# 780-00055_rev1_CPLD_SCH_NRES_RTD_board.net
KiCad netlist of a schematic drawn in Altium Designer
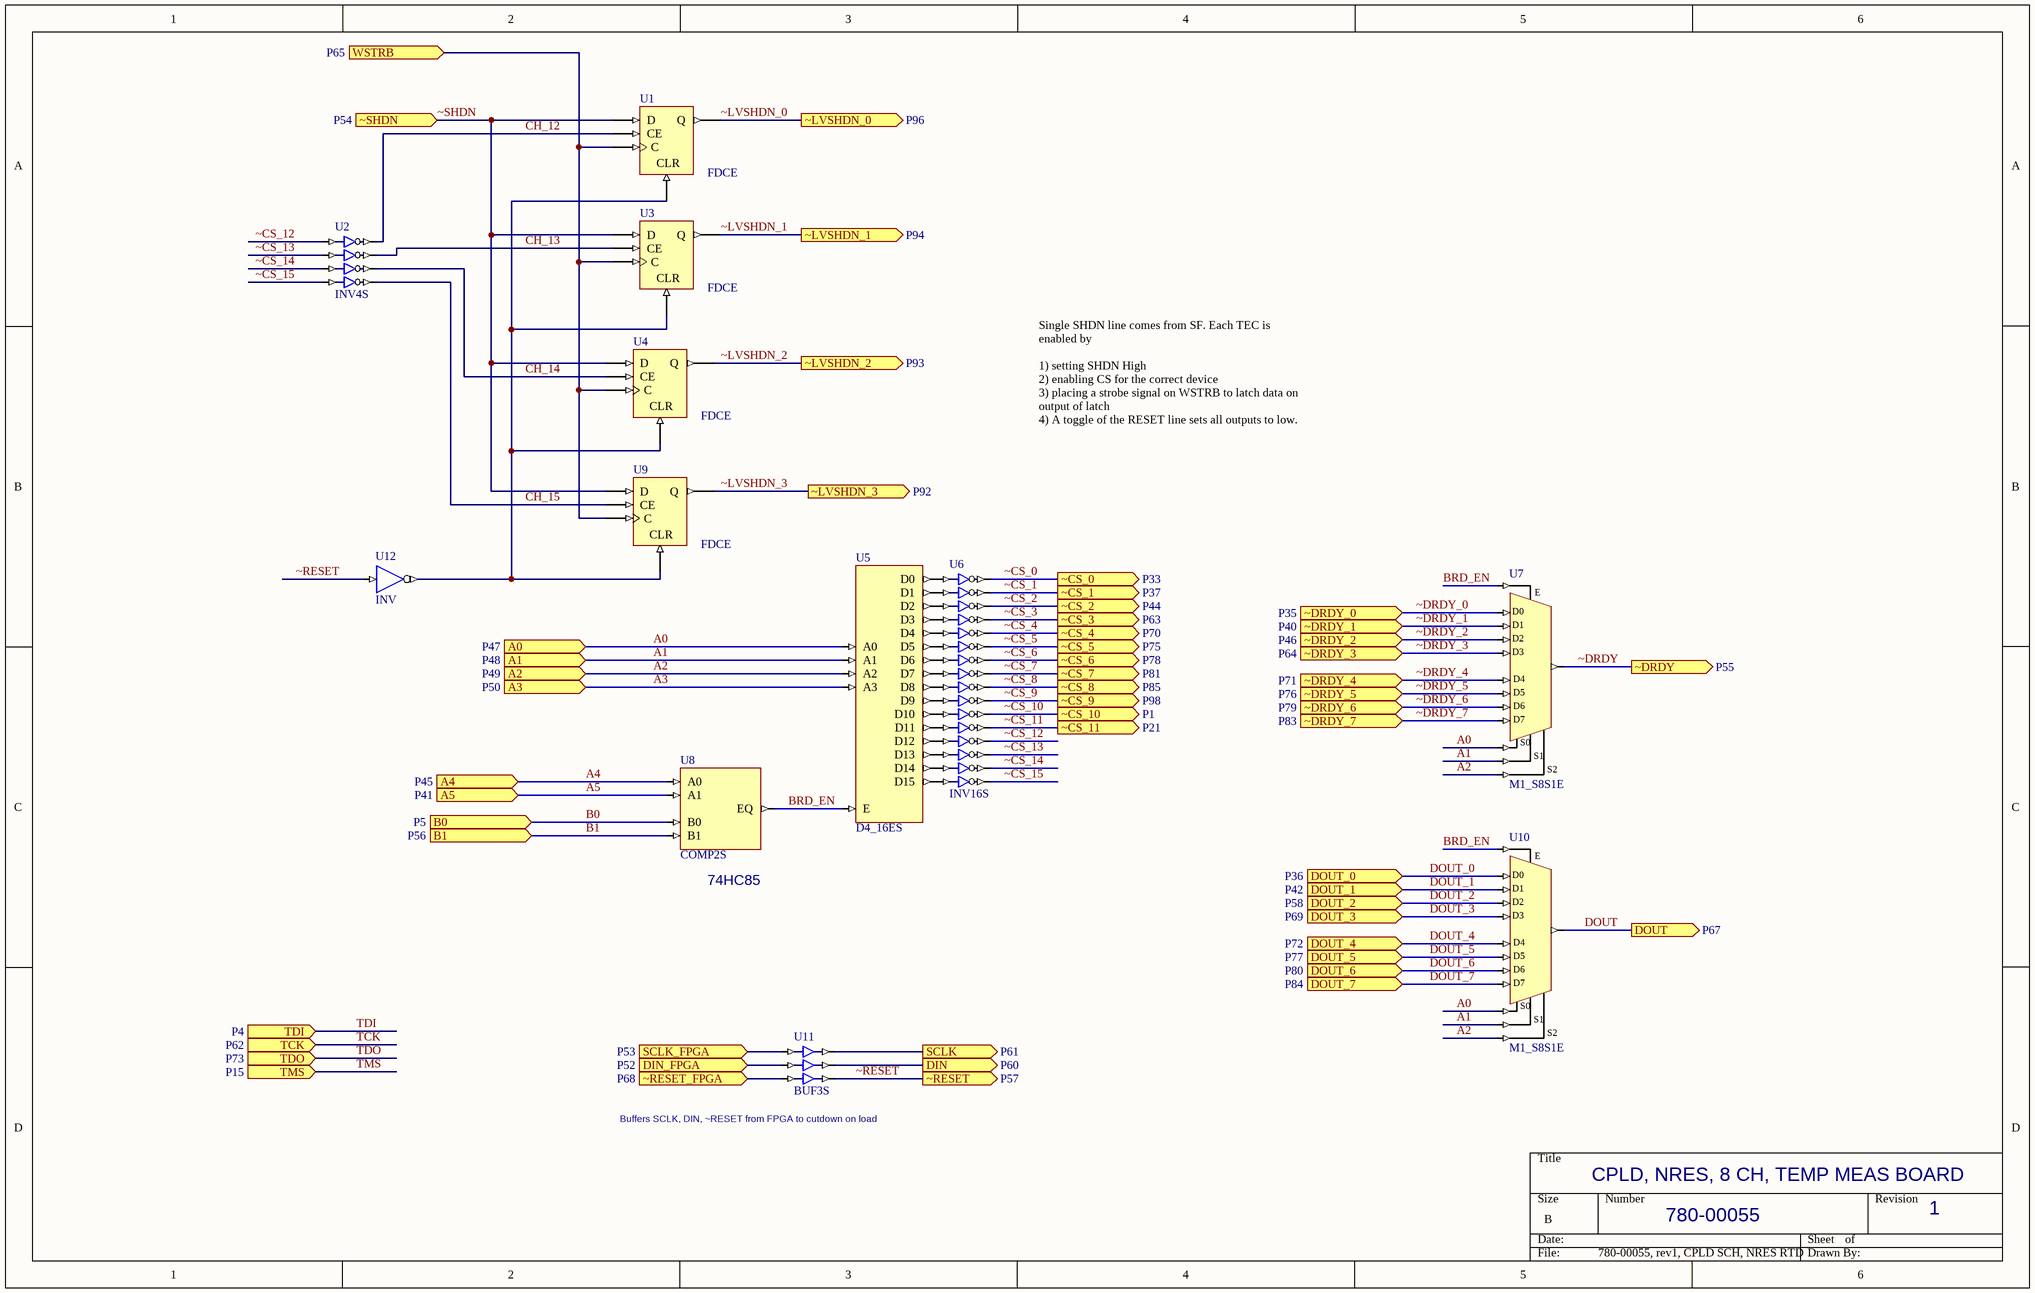
[diagram p0: 780-00055, rev1, CPLD SCH, NRES RTD board.SchDoc]

(export (version "E")
  (design (tool "Eeschema 10.0.6"))
  (components
    (comp (ref "U1")
      (value "FDCE")
      (description "D Flip-Flop with Clock Enable and Asynchronous Clear")
      (fields (field (name "PUBLISHER") "Altium Limited"))
      (libsource (lib "Xilinx CoolRunner-XPLA3 FPGA") (part "FDCE"))
    )
    (comp (ref "U2")
      (value "INV4S")
      (description "4-Bit Inverter, Single Pin Version")
      (fields (field (name "PUBLISHER") "Altium Limited"))
      (libsource (lib "FPGA Generic") (part "INV4S"))
    )
    (comp (ref "U3")
      (value "FDCE")
      (description "D Flip-Flop with Clock Enable and Asynchronous Clear")
      (fields (field (name "PUBLISHER") "Altium Limited"))
      (libsource (lib "Xilinx CoolRunner-XPLA3 FPGA") (part "FDCE"))
    )
    (comp (ref "U4")
      (value "FDCE")
      (description "D Flip-Flop with Clock Enable and Asynchronous Clear")
      (fields (field (name "PUBLISHER") "Altium Limited"))
      (libsource (lib "Xilinx CoolRunner-XPLA3 FPGA") (part "FDCE"))
    )
    (comp (ref "U5")
      (value "D4_16ES")
      (description "Binary 4- to 16-Bit Decoder with Enable, Single Pin Version")
      (fields (field (name "PUBLISHER") "Altium Limited"))
      (libsource (lib "FPGA Generic") (part "D4_16ES"))
    )
    (comp (ref "U6")
      (value "INV16S")
      (description "16-Bit Inverter, Single Pin Version")
      (fields (field (name "PUBLISHER") "Altium Limited"))
      (libsource (lib "FPGA Generic") (part "INV16S"))
    )
    (comp (ref "U7")
      (value "M1_S8S1E")
      (description "8x1-Single Wire to 1x1-Single Wire Multiplexer With Enable")
      (fields (field (name "PUBLISHER") "Altium Limited"))
      (libsource (lib "FPGA Generic") (part "M1_S8S1E"))
    )
    (comp (ref "U8")
      (value "COMP2S")
      (description "2-Bit Identity Comparator, Single Pin Version")
      (fields (field (name "PUBLISHER") "Altium Limited"))
      (libsource (lib "FPGA Generic") (part "COMP2S"))
    )
    (comp (ref "U9")
      (value "FDCE")
      (description "D Flip-Flop with Clock Enable and Asynchronous Clear")
      (fields (field (name "PUBLISHER") "Altium Limited"))
      (libsource (lib "Xilinx CoolRunner-XPLA3 FPGA") (part "FDCE"))
    )
    (comp (ref "U10")
      (value "M1_S8S1E")
      (description "8x1-Single Wire to 1x1-Single Wire Multiplexer With Enable")
      (fields (field (name "PUBLISHER") "Altium Limited"))
      (libsource (lib "FPGA Generic") (part "M1_S8S1E"))
    )
    (comp (ref "U11")
      (value "BUF3S")
      (description "3-Bit General Purpose (Non-inverting) Buffer, Single Pin Version")
      (fields (field (name "PUBLISHER") "Altium Limited"))
      (libsource (lib "FPGA Generic") (part "BUF3S"))
    )
    (comp (ref "U12")
      (value "INV")
      (description "Inverter")
      (fields (field (name "PUBLISHER") "Altium Limited"))
      (libsource (lib "FPGA Generic") (part "INV"))
    )
  )
  (nets
    (net (code "1") (name "/A0") (class "Default")
      (node (ref "U10") (pin "S0") (pinfunction "S0_S0") (pintype "input"))
      (node (ref "U5") (pin "A0") (pinfunction "A0_A0") (pintype "input"))
      (node (ref "U7") (pin "S0") (pinfunction "S0_S0") (pintype "input"))
    )
    (net (code "2") (name "/A1") (class "Default")
      (node (ref "U10") (pin "S1") (pinfunction "S1_S1") (pintype "input"))
      (node (ref "U5") (pin "A1") (pinfunction "A1_A1") (pintype "input"))
      (node (ref "U7") (pin "S1") (pinfunction "S1_S1") (pintype "input"))
    )
    (net (code "3") (name "/A2") (class "Default")
      (node (ref "U10") (pin "S2") (pinfunction "S2_S2") (pintype "input"))
      (node (ref "U5") (pin "A2") (pinfunction "A2_A2") (pintype "input"))
      (node (ref "U7") (pin "S2") (pinfunction "S2_S2") (pintype "input"))
    )
    (net (code "4") (name "/A3") (class "Default")
      (node (ref "U5") (pin "A3") (pinfunction "A3_A3") (pintype "input"))
    )
    (net (code "5") (name "/A4") (class "Default")
      (node (ref "U8") (pin "A0") (pinfunction "A0_A0") (pintype "input"))
    )
    (net (code "6") (name "/A5") (class "Default")
      (node (ref "U8") (pin "A1") (pinfunction "A1_A1") (pintype "input"))
    )
    (net (code "7") (name "/B0") (class "Default")
      (node (ref "U8") (pin "B0") (pinfunction "B0_B0") (pintype "input"))
    )
    (net (code "8") (name "/B1") (class "Default")
      (node (ref "U8") (pin "B1") (pinfunction "B1_B1") (pintype "input"))
    )
    (net (code "9") (name "/BRD_EN") (class "Default")
      (node (ref "U10") (pin "E") (pinfunction "E_E") (pintype "input"))
      (node (ref "U5") (pin "E") (pinfunction "E_E") (pintype "input"))
      (node (ref "U7") (pin "E") (pinfunction "E_E") (pintype "input"))
      (node (ref "U8") (pin "EQ") (pinfunction "EQ_EQ") (pintype "output"))
    )
    (net (code "10") (name "/CH_12") (class "Default")
      (node (ref "U1") (pin "CE") (pinfunction "CE_CE") (pintype "input"))
      (node (ref "U2") (pin "O0") (pinfunction "O0_O0") (pintype "output"))
    )
    (net (code "11") (name "/CH_13") (class "Default")
      (node (ref "U2") (pin "O1") (pinfunction "O1_O1") (pintype "output"))
      (node (ref "U3") (pin "CE") (pinfunction "CE_CE") (pintype "input"))
    )
    (net (code "12") (name "/CH_14") (class "Default")
      (node (ref "U2") (pin "O2") (pinfunction "O2_O2") (pintype "output"))
      (node (ref "U4") (pin "CE") (pinfunction "CE_CE") (pintype "input"))
    )
    (net (code "13") (name "/CH_15") (class "Default")
      (node (ref "U2") (pin "O3") (pinfunction "O3_O3") (pintype "output"))
      (node (ref "U9") (pin "CE") (pinfunction "CE_CE") (pintype "input"))
    )
    (net (code "14") (name "/DIN") (class "Default")
      (node (ref "U11") (pin "O1") (pinfunction "O1_O1") (pintype "output"))
    )
    (net (code "15") (name "/DIN_FPGA") (class "Default")
      (node (ref "U11") (pin "I1") (pinfunction "I1_I1") (pintype "input"))
    )
    (net (code "16") (name "/DOUT") (class "Default")
      (node (ref "U10") (pin "O") (pinfunction "O_O") (pintype "output"))
    )
    (net (code "17") (name "/DOUT_0") (class "Default")
      (node (ref "U10") (pin "D0") (pinfunction "D0_D0") (pintype "input"))
    )
    (net (code "18") (name "/DOUT_1") (class "Default")
      (node (ref "U10") (pin "D1") (pinfunction "D1_D1") (pintype "input"))
    )
    (net (code "19") (name "/DOUT_2") (class "Default")
      (node (ref "U10") (pin "D2") (pinfunction "D2_D2") (pintype "input"))
    )
    (net (code "20") (name "/DOUT_3") (class "Default")
      (node (ref "U10") (pin "D3") (pinfunction "D3_D3") (pintype "input"))
    )
    (net (code "21") (name "/DOUT_4") (class "Default")
      (node (ref "U10") (pin "D4") (pinfunction "D4_D4") (pintype "input"))
    )
    (net (code "22") (name "/DOUT_5") (class "Default")
      (node (ref "U10") (pin "D5") (pinfunction "D5_D5") (pintype "input"))
    )
    (net (code "23") (name "/DOUT_6") (class "Default")
      (node (ref "U10") (pin "D6") (pinfunction "D6_D6") (pintype "input"))
    )
    (net (code "24") (name "/DOUT_7") (class "Default")
      (node (ref "U10") (pin "D7") (pinfunction "D7_D7") (pintype "input"))
    )
    (net (code "25") (name "/SCLK") (class "Default")
      (node (ref "U11") (pin "O0") (pinfunction "O0_O0") (pintype "output"))
    )
    (net (code "26") (name "/SCLK_FPGA") (class "Default")
      (node (ref "U11") (pin "I0") (pinfunction "I0_I0") (pintype "input"))
    )
    (net (code "31") (name "/WSTRB") (class "Default")
      (node (ref "U1") (pin "C") (pinfunction "C_C") (pintype "input"))
      (node (ref "U3") (pin "C") (pinfunction "C_C") (pintype "input"))
      (node (ref "U4") (pin "C") (pinfunction "C_C") (pintype "input"))
      (node (ref "U9") (pin "C") (pinfunction "C_C") (pintype "input"))
    )
    (net (code "32") (name "/~CS_0") (class "Default")
      (node (ref "U6") (pin "O0") (pinfunction "O0_O0") (pintype "output"))
    )
    (net (code "33") (name "/~CS_1") (class "Default")
      (node (ref "U6") (pin "O1") (pinfunction "O1_O1") (pintype "output"))
    )
    (net (code "34") (name "/~CS_2") (class "Default")
      (node (ref "U6") (pin "O2") (pinfunction "O2_O2") (pintype "output"))
    )
    (net (code "35") (name "/~CS_3") (class "Default")
      (node (ref "U6") (pin "O3") (pinfunction "O3_O3") (pintype "output"))
    )
    (net (code "36") (name "/~CS_4") (class "Default")
      (node (ref "U6") (pin "O4") (pinfunction "O4_O4") (pintype "output"))
    )
    (net (code "37") (name "/~CS_5") (class "Default")
      (node (ref "U6") (pin "O5") (pinfunction "O5_O5") (pintype "output"))
    )
    (net (code "38") (name "/~CS_6") (class "Default")
      (node (ref "U6") (pin "O6") (pinfunction "O6_O6") (pintype "output"))
    )
    (net (code "39") (name "/~CS_7") (class "Default")
      (node (ref "U6") (pin "O7") (pinfunction "O7_O7") (pintype "output"))
    )
    (net (code "40") (name "/~CS_8") (class "Default")
      (node (ref "U6") (pin "O8") (pinfunction "O8_O8") (pintype "output"))
    )
    (net (code "41") (name "/~CS_9") (class "Default")
      (node (ref "U6") (pin "O9") (pinfunction "O9_O9") (pintype "output"))
    )
    (net (code "42") (name "/~CS_10") (class "Default")
      (node (ref "U6") (pin "O10") (pinfunction "O10_O10") (pintype "output"))
    )
    (net (code "43") (name "/~CS_11") (class "Default")
      (node (ref "U6") (pin "O11") (pinfunction "O11_O11") (pintype "output"))
    )
    (net (code "44") (name "/~CS_12") (class "Default")
      (node (ref "U2") (pin "I0") (pinfunction "I0_I0") (pintype "input"))
      (node (ref "U6") (pin "O12") (pinfunction "O12_O12") (pintype "output"))
    )
    (net (code "45") (name "/~CS_13") (class "Default")
      (node (ref "U2") (pin "I1") (pinfunction "I1_I1") (pintype "input"))
      (node (ref "U6") (pin "O13") (pinfunction "O13_O13") (pintype "output"))
    )
    (net (code "46") (name "/~CS_14") (class "Default")
      (node (ref "U2") (pin "I2") (pinfunction "I2_I2") (pintype "input"))
      (node (ref "U6") (pin "O14") (pinfunction "O14_O14") (pintype "output"))
    )
    (net (code "47") (name "/~CS_15") (class "Default")
      (node (ref "U2") (pin "I3") (pinfunction "I3_I3") (pintype "input"))
      (node (ref "U6") (pin "O15") (pinfunction "O15_O15") (pintype "output"))
    )
    (net (code "48") (name "/~DRDY") (class "Default")
      (node (ref "U7") (pin "O") (pinfunction "O_O") (pintype "output"))
    )
    (net (code "49") (name "/~DRDY_0") (class "Default")
      (node (ref "U7") (pin "D0") (pinfunction "D0_D0") (pintype "input"))
    )
    (net (code "50") (name "/~DRDY_1") (class "Default")
      (node (ref "U7") (pin "D1") (pinfunction "D1_D1") (pintype "input"))
    )
    (net (code "51") (name "/~DRDY_2") (class "Default")
      (node (ref "U7") (pin "D2") (pinfunction "D2_D2") (pintype "input"))
    )
    (net (code "52") (name "/~DRDY_3") (class "Default")
      (node (ref "U7") (pin "D3") (pinfunction "D3_D3") (pintype "input"))
    )
    (net (code "53") (name "/~DRDY_4") (class "Default")
      (node (ref "U7") (pin "D4") (pinfunction "D4_D4") (pintype "input"))
    )
    (net (code "54") (name "/~DRDY_5") (class "Default")
      (node (ref "U7") (pin "D5") (pinfunction "D5_D5") (pintype "input"))
    )
    (net (code "55") (name "/~DRDY_6") (class "Default")
      (node (ref "U7") (pin "D6") (pinfunction "D6_D6") (pintype "input"))
    )
    (net (code "56") (name "/~DRDY_7") (class "Default")
      (node (ref "U7") (pin "D7") (pinfunction "D7_D7") (pintype "input"))
    )
    (net (code "57") (name "/~LVSHDN_0") (class "Default")
      (node (ref "U1") (pin "Q") (pinfunction "Q_Q") (pintype "output"))
    )
    (net (code "58") (name "/~LVSHDN_1") (class "Default")
      (node (ref "U3") (pin "Q") (pinfunction "Q_Q") (pintype "output"))
    )
    (net (code "59") (name "/~LVSHDN_2") (class "Default")
      (node (ref "U4") (pin "Q") (pinfunction "Q_Q") (pintype "output"))
    )
    (net (code "60") (name "/~LVSHDN_3") (class "Default")
      (node (ref "U9") (pin "Q") (pinfunction "Q_Q") (pintype "output"))
    )
    (net (code "61") (name "/~RESET") (class "Default")
      (node (ref "U11") (pin "O2") (pinfunction "O2_O2") (pintype "output"))
      (node (ref "U12") (pin "I") (pinfunction "I_I") (pintype "input"))
    )
    (net (code "62") (name "/~RESET_FPGA") (class "Default")
      (node (ref "U11") (pin "I2") (pinfunction "I2_I2") (pintype "input"))
    )
    (net (code "63") (name "/~SHDN") (class "Default")
      (node (ref "U1") (pin "D") (pinfunction "D_D") (pintype "input"))
      (node (ref "U3") (pin "D") (pinfunction "D_D") (pintype "input"))
      (node (ref "U4") (pin "D") (pinfunction "D_D") (pintype "input"))
      (node (ref "U9") (pin "D") (pinfunction "D_D") (pintype "input"))
    )
    (net (code "64") (name "Net-(U1-PadCLR)") (class "Default")
      (node (ref "U1") (pin "CLR") (pinfunction "CLR_CLR") (pintype "input"))
      (node (ref "U12") (pin "O") (pinfunction "O_O") (pintype "output"))
      (node (ref "U3") (pin "CLR") (pinfunction "CLR_CLR") (pintype "input"))
      (node (ref "U4") (pin "CLR") (pinfunction "CLR_CLR") (pintype "input"))
      (node (ref "U9") (pin "CLR") (pinfunction "CLR_CLR") (pintype "input"))
    )
    (net (code "65") (name "Net-(U5-PadD0)") (class "Default")
      (node (ref "U5") (pin "D0") (pinfunction "D0_D0") (pintype "output"))
      (node (ref "U6") (pin "I0") (pinfunction "I0_I0") (pintype "input"))
    )
    (net (code "66") (name "Net-(U5-PadD1)") (class "Default")
      (node (ref "U5") (pin "D1") (pinfunction "D1_D1") (pintype "output"))
      (node (ref "U6") (pin "I1") (pinfunction "I1_I1") (pintype "input"))
    )
    (net (code "67") (name "Net-(U5-PadD2)") (class "Default")
      (node (ref "U5") (pin "D2") (pinfunction "D2_D2") (pintype "output"))
      (node (ref "U6") (pin "I2") (pinfunction "I2_I2") (pintype "input"))
    )
    (net (code "68") (name "Net-(U5-PadD3)") (class "Default")
      (node (ref "U5") (pin "D3") (pinfunction "D3_D3") (pintype "output"))
      (node (ref "U6") (pin "I3") (pinfunction "I3_I3") (pintype "input"))
    )
    (net (code "69") (name "Net-(U5-PadD4)") (class "Default")
      (node (ref "U5") (pin "D4") (pinfunction "D4_D4") (pintype "output"))
      (node (ref "U6") (pin "I4") (pinfunction "I4_I4") (pintype "input"))
    )
    (net (code "70") (name "Net-(U5-PadD5)") (class "Default")
      (node (ref "U5") (pin "D5") (pinfunction "D5_D5") (pintype "output"))
      (node (ref "U6") (pin "I5") (pinfunction "I5_I5") (pintype "input"))
    )
    (net (code "71") (name "Net-(U5-PadD6)") (class "Default")
      (node (ref "U5") (pin "D6") (pinfunction "D6_D6") (pintype "output"))
      (node (ref "U6") (pin "I6") (pinfunction "I6_I6") (pintype "input"))
    )
    (net (code "72") (name "Net-(U5-PadD7)") (class "Default")
      (node (ref "U5") (pin "D7") (pinfunction "D7_D7") (pintype "output"))
      (node (ref "U6") (pin "I7") (pinfunction "I7_I7") (pintype "input"))
    )
    (net (code "73") (name "Net-(U5-PadD8)") (class "Default")
      (node (ref "U5") (pin "D8") (pinfunction "D8_D8") (pintype "output"))
      (node (ref "U6") (pin "I8") (pinfunction "I8_I8") (pintype "input"))
    )
    (net (code "74") (name "Net-(U5-PadD9)") (class "Default")
      (node (ref "U5") (pin "D9") (pinfunction "D9_D9") (pintype "output"))
      (node (ref "U6") (pin "I9") (pinfunction "I9_I9") (pintype "input"))
    )
    (net (code "75") (name "Net-(U5-PadD10)") (class "Default")
      (node (ref "U5") (pin "D10") (pinfunction "D10_D10") (pintype "output"))
      (node (ref "U6") (pin "I10") (pinfunction "I10_I10") (pintype "input"))
    )
    (net (code "76") (name "Net-(U5-PadD11)") (class "Default")
      (node (ref "U5") (pin "D11") (pinfunction "D11_D11") (pintype "output"))
      (node (ref "U6") (pin "I11") (pinfunction "I11_I11") (pintype "input"))
    )
    (net (code "77") (name "Net-(U5-PadD12)") (class "Default")
      (node (ref "U5") (pin "D12") (pinfunction "D12_D12") (pintype "output"))
      (node (ref "U6") (pin "I12") (pinfunction "I12_I12") (pintype "input"))
    )
    (net (code "78") (name "Net-(U5-PadD13)") (class "Default")
      (node (ref "U5") (pin "D13") (pinfunction "D13_D13") (pintype "output"))
      (node (ref "U6") (pin "I13") (pinfunction "I13_I13") (pintype "input"))
    )
    (net (code "79") (name "Net-(U5-PadD14)") (class "Default")
      (node (ref "U5") (pin "D14") (pinfunction "D14_D14") (pintype "output"))
      (node (ref "U6") (pin "I14") (pinfunction "I14_I14") (pintype "input"))
    )
    (net (code "80") (name "Net-(U5-PadD15)") (class "Default")
      (node (ref "U5") (pin "D15") (pinfunction "D15_D15") (pintype "output"))
      (node (ref "U6") (pin "I15") (pinfunction "I15_I15") (pintype "input"))
    )
  )
)
